# PE_RM.net
KiCad netlist of a schematic drawn in EAGLE
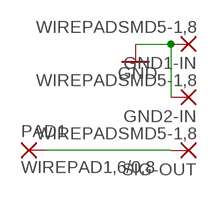
[diagram p0: schematic, sheet 1]

(export (version "E")
  (design (tool "Eeschema 10.0.6"))
  (components
    (comp (ref "GND1-IN")
      (value "WIREPADSMD5-1,8")
      (footprint "eagle-import:5-1,8")
      (libsource (lib "eagle-import") (part "WIREPADSMD5-1,8"))
    )
    (comp (ref "GND2-IN")
      (value "WIREPADSMD5-1,8")
      (footprint "eagle-import:5-1,8")
      (libsource (lib "eagle-import") (part "WIREPADSMD5-1,8"))
    )
    (comp (ref "PAD1")
      (value "WIREPAD1,6/0,8")
      (footprint "eagle-import:1,6_0,8")
      (libsource (lib "eagle-import") (part "WIREPAD1,6/0,8"))
    )
    (comp (ref "SIG-OUT")
      (value "WIREPADSMD5-1,8")
      (footprint "eagle-import:5-1,8")
      (libsource (lib "eagle-import") (part "WIREPADSMD5-1,8"))
    )
  )
  (nets
    (net (code "1") (name "GND") (class "Default")
      (node (ref "GND1-IN") (pin "1") (pinfunction "P_1") (pintype "passive"))
      (node (ref "GND2-IN") (pin "1") (pinfunction "P_1") (pintype "passive"))
    )
    (net (code "2") (name "Net-(PAD1-P)") (class "Default")
      (node (ref "PAD1") (pin "1") (pinfunction "P_1") (pintype "passive"))
      (node (ref "SIG-OUT") (pin "1") (pinfunction "P_1") (pintype "passive"))
    )
  )
)
